# TSOC_GROVEY_ONE_R0_0.net
KiCad netlist of a schematic drawn in EAGLE
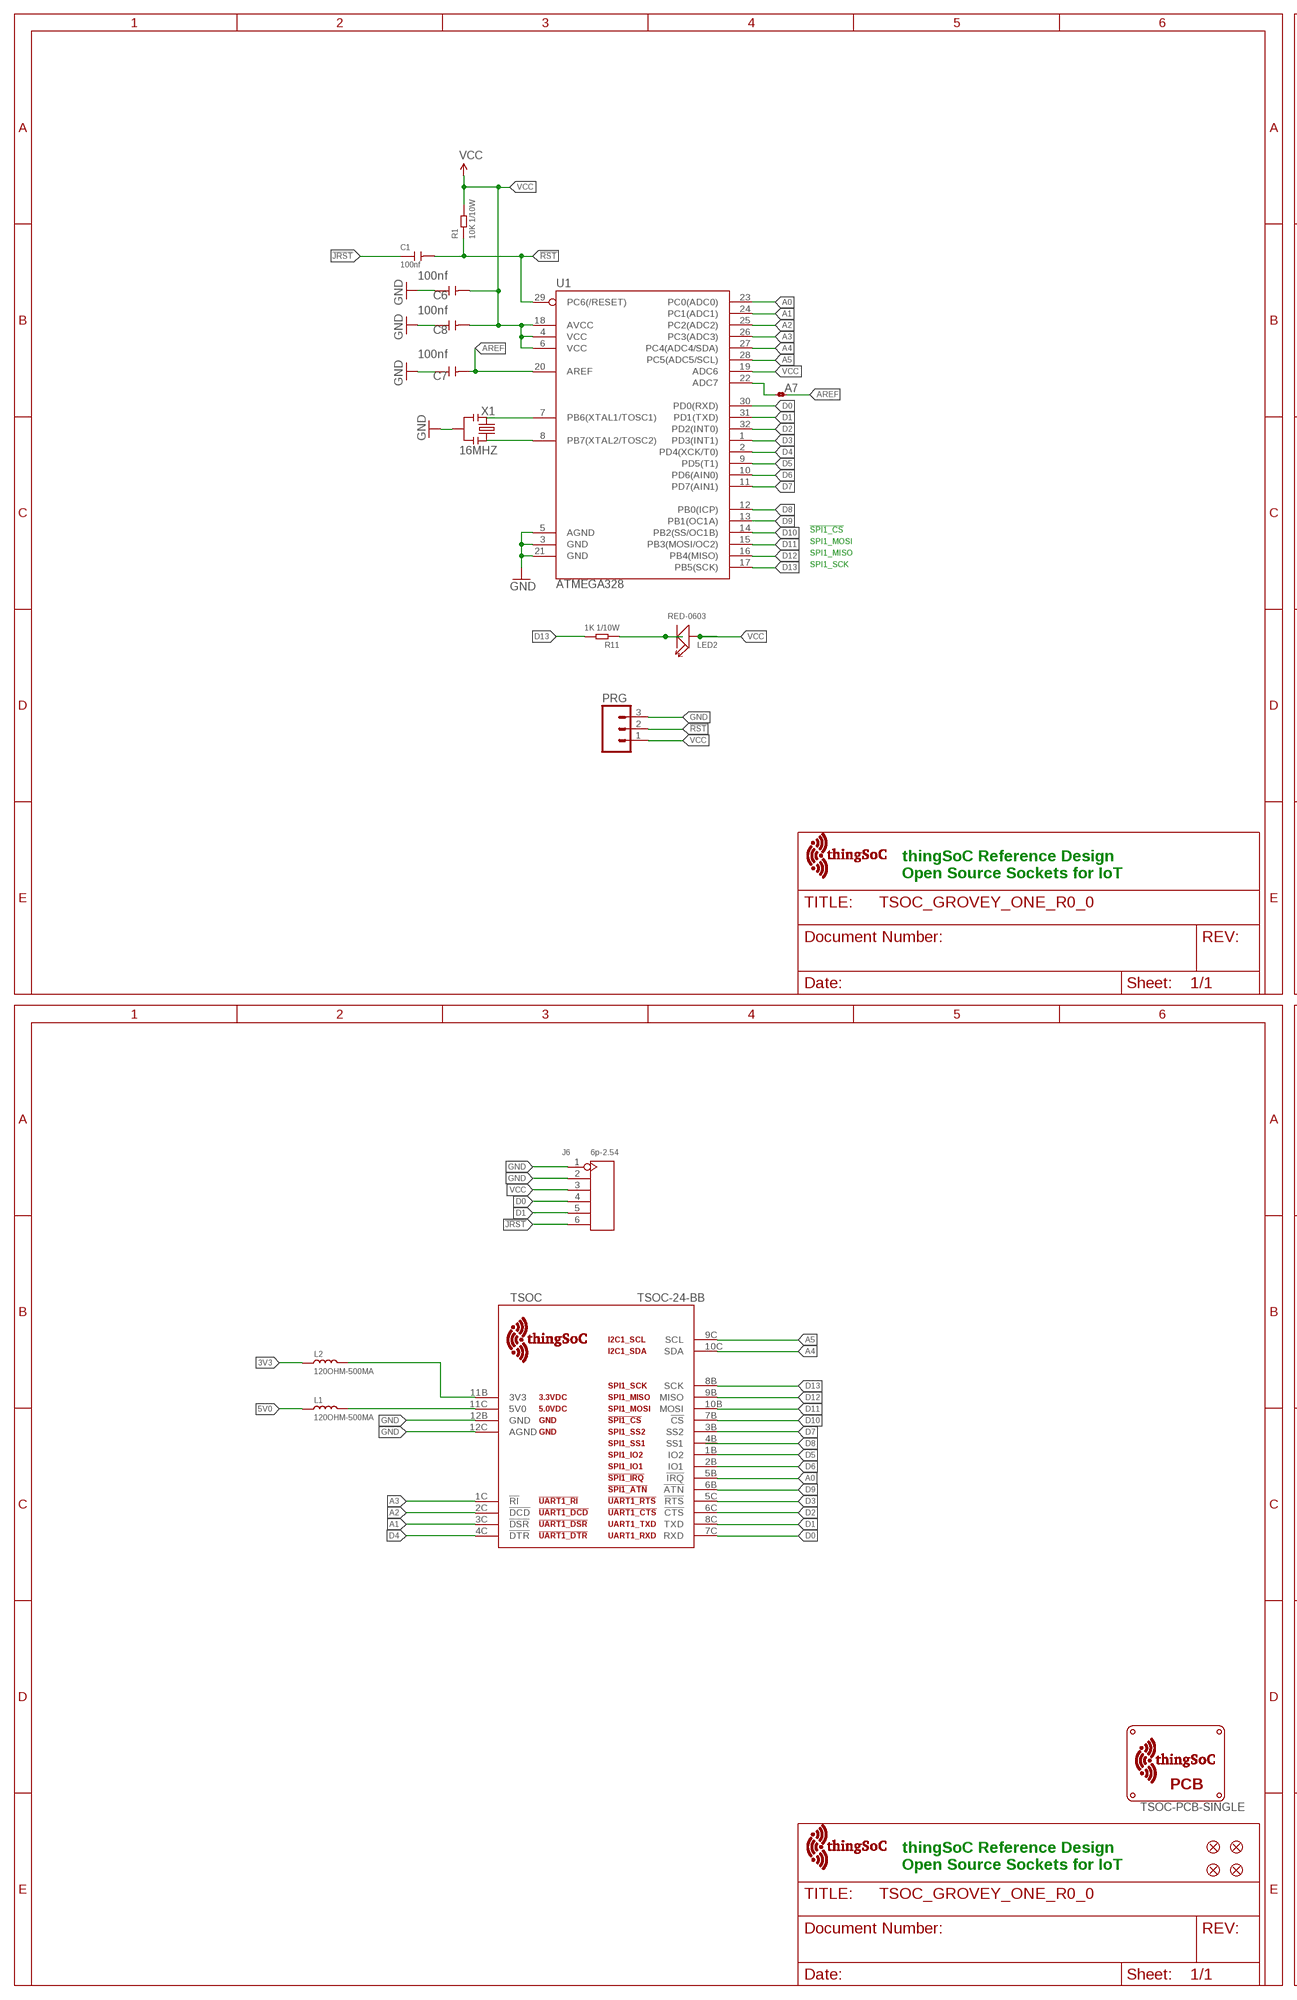
[diagram p0: schematic, sheet 1, part 1 of 2]
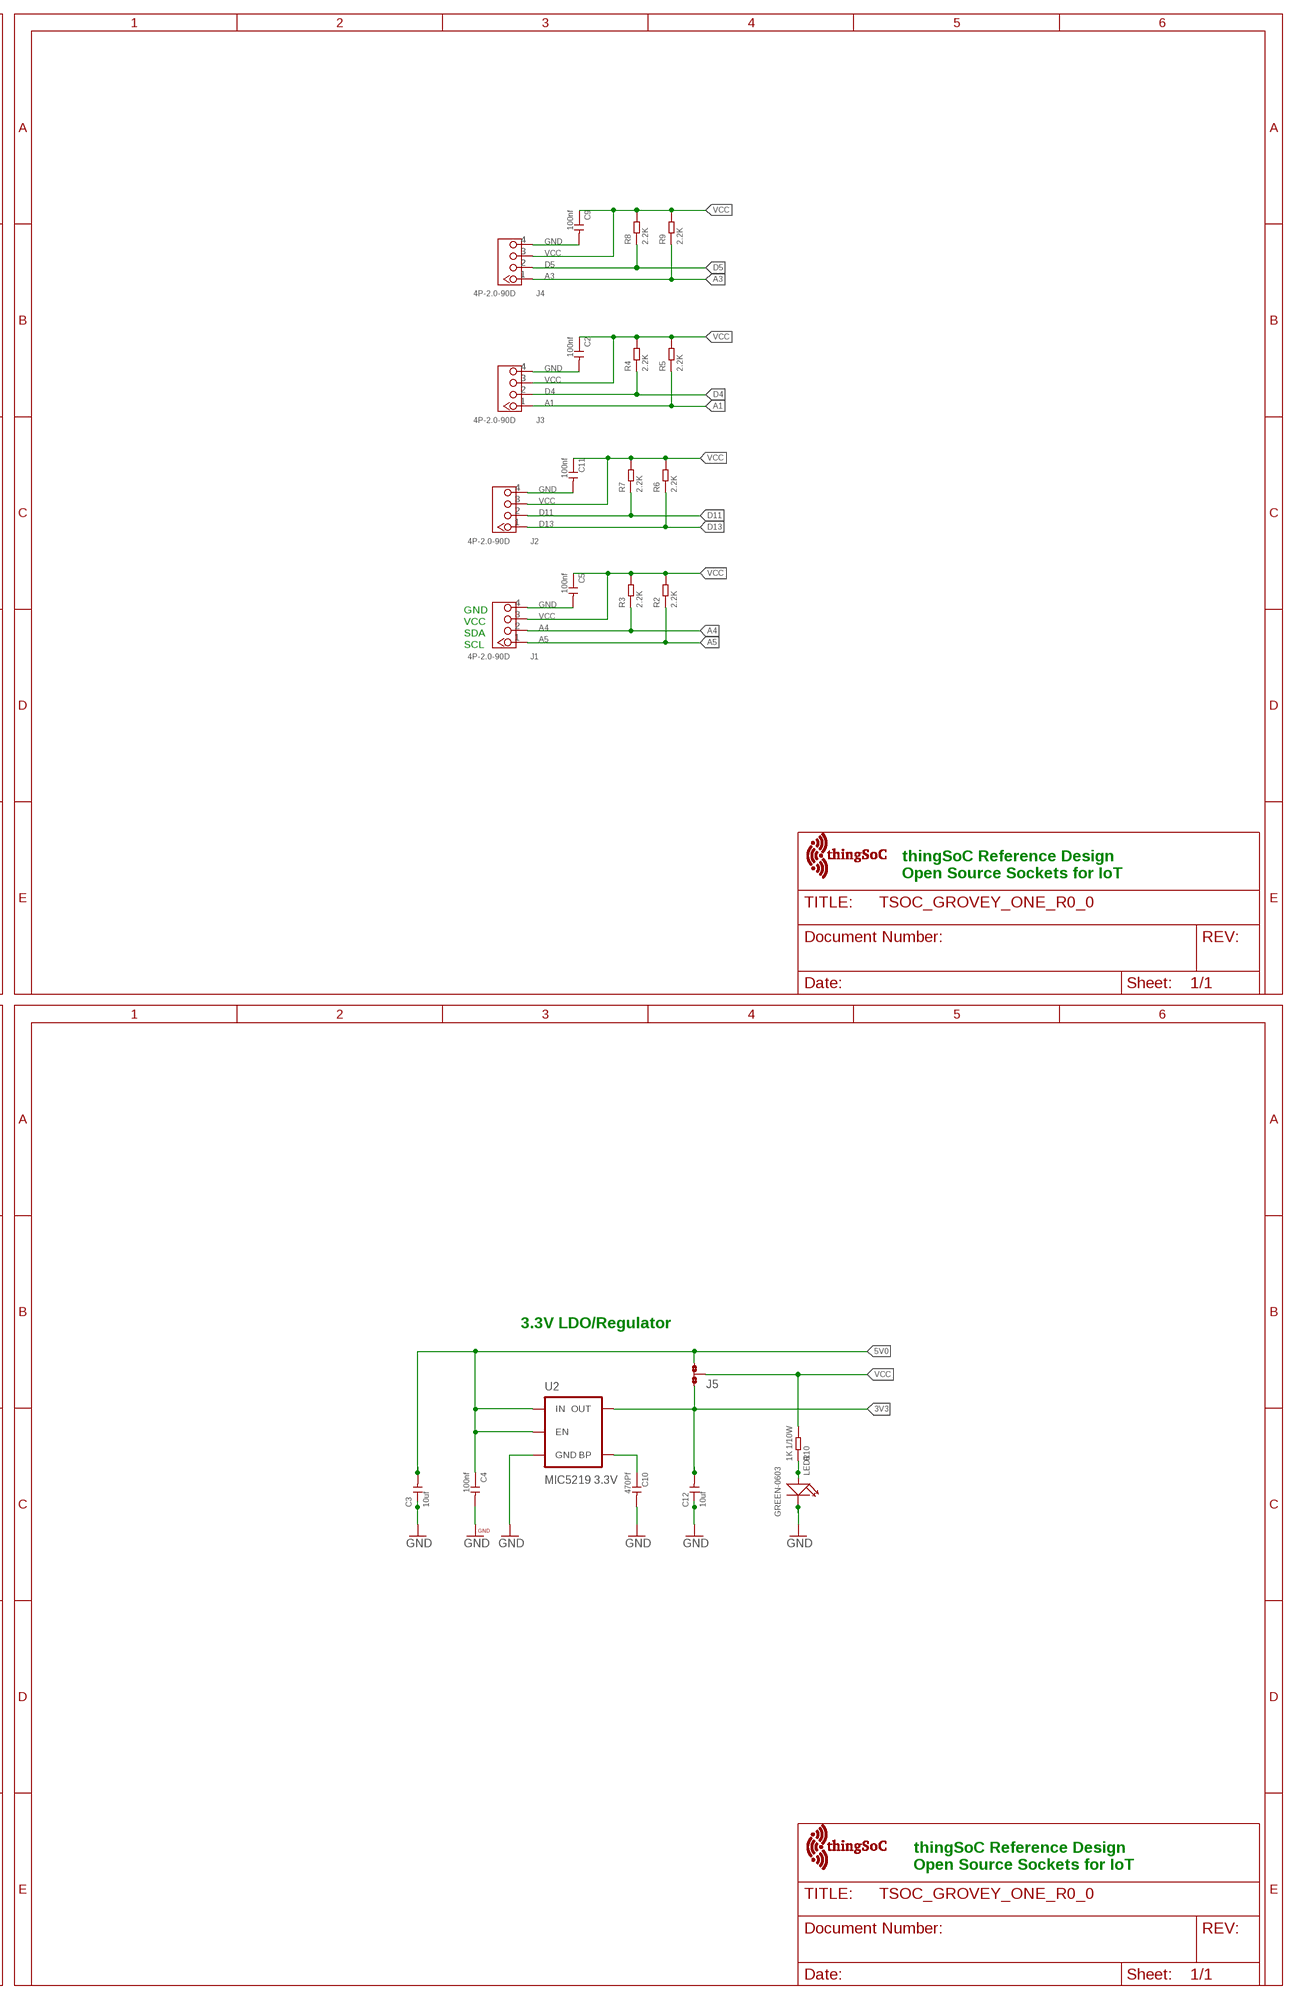
[diagram p1: schematic, sheet 1, part 2 of 2]

(export (version "E")
  (design (tool "Eeschema 10.0.6"))
  (components
    (comp (ref "$$U$2")
      (value "TSOC-PCB-SINGLE")
      (footprint "eagle-import:TSOC-BB-BRD-DIM")
      (libsource (lib "eagle-import") (part "TSOC-PCB-SINGLE"))
    )
    (comp (ref "A7")
      (value "JMP-2-NO")
      (footprint "eagle-import:JMP-2-NO")
      (libsource (lib "eagle-import") (part "JMP-2-NO"))
    )
    (comp (ref "C1")
      (value "100nf")
      (footprint "eagle-import:C0603")
      (fields (field (name "MPN") "CC0603KRX7R9BB104"))
      (libsource (lib "eagle-import") (part "CERAMIC-100NF-50V-10%-X7R(0603)"))
    )
    (comp (ref "C2")
      (value "100nf")
      (footprint "eagle-import:C0603")
      (fields (field (name "MPN") "CC0603KRX7R9BB104"))
      (libsource (lib "eagle-import") (part "CERAMIC-100NF-50V-10%-X7R(0603)"))
    )
    (comp (ref "C3")
      (value "10uf")
      (footprint "eagle-import:C0603")
      (fields (field (name "MPN") "CC0603KRX5R6BB106"))
      (libsource (lib "eagle-import") (part "CERAMIC-10UF-10V-10%-X5R(0603)"))
    )
    (comp (ref "C4")
      (value "100nf")
      (footprint "eagle-import:C0603")
      (fields (field (name "MPN") "CC0603KRX7R9BB104"))
      (libsource (lib "eagle-import") (part "CERAMIC-100NF-50V-10%-X7R(0603)"))
    )
    (comp (ref "C5")
      (value "100nf")
      (footprint "eagle-import:C0603")
      (fields (field (name "MPN") "CC0603KRX7R9BB104"))
      (libsource (lib "eagle-import") (part "CERAMIC-100NF-50V-10%-X7R(0603)"))
    )
    (comp (ref "C6")
      (value "100nf")
      (footprint "eagle-import:C0603")
      (fields (field (name "MPN") "CC0603KRX7R9BB104"))
      (libsource (lib "eagle-import") (part "CERAMIC-100NF-50V-10%-X7R(0603)"))
    )
    (comp (ref "C7")
      (value "100nf")
      (footprint "eagle-import:C0603")
      (fields (field (name "MPN") "CC0603KRX7R9BB104"))
      (libsource (lib "eagle-import") (part "CERAMIC-100NF-50V-10%-X7R(0603)"))
    )
    (comp (ref "C8")
      (value "100nf")
      (footprint "eagle-import:C0603")
      (fields (field (name "MPN") "CC0603KRX7R9BB104"))
      (libsource (lib "eagle-import") (part "CERAMIC-100NF-50V-10%-X7R(0603)"))
    )
    (comp (ref "C9")
      (value "100nf")
      (footprint "eagle-import:C0603")
      (fields (field (name "MPN") "CC0603KRX7R9BB104"))
      (libsource (lib "eagle-import") (part "CERAMIC-100NF-50V-10%-X7R(0603)"))
    )
    (comp (ref "C10")
      (value "470Pf")
      (footprint "eagle-import:C0603")
      (fields (field (name "MPN") "CC0603KRX7R9BB104"))
      (libsource (lib "eagle-import") (part "CERAMIC-100NF-50V-10%-X7R(0603)"))
    )
    (comp (ref "C11")
      (value "100nf")
      (footprint "eagle-import:C0603")
      (fields (field (name "MPN") "CC0603KRX7R9BB104"))
      (libsource (lib "eagle-import") (part "CERAMIC-100NF-50V-10%-X7R(0603)"))
    )
    (comp (ref "C12")
      (value "10uf")
      (footprint "eagle-import:C0603")
      (fields (field (name "MPN") "CC0603KRX5R6BB106"))
      (libsource (lib "eagle-import") (part "CERAMIC-10UF-10V-10%-X5R(0603)"))
    )
    (comp (ref "FID1")
      (value "FIDUCIALUFIDUCIAL")
      (footprint "eagle-import:MICRO-FIDUCIAL")
      (libsource (lib "eagle-import") (part "FIDUCIALUFIDUCIAL"))
    )
    (comp (ref "FID2")
      (value "FIDUCIALUFIDUCIAL")
      (footprint "eagle-import:MICRO-FIDUCIAL")
      (libsource (lib "eagle-import") (part "FIDUCIALUFIDUCIAL"))
    )
    (comp (ref "FID3")
      (value "FIDUCIALUFIDUCIAL")
      (footprint "eagle-import:MICRO-FIDUCIAL")
      (libsource (lib "eagle-import") (part "FIDUCIALUFIDUCIAL"))
    )
    (comp (ref "FID4")
      (value "FIDUCIALUFIDUCIAL")
      (footprint "eagle-import:MICRO-FIDUCIAL")
      (libsource (lib "eagle-import") (part "FIDUCIALUFIDUCIAL"))
    )
    (comp (ref "J1")
      (value "4P-2.0-90D")
      (footprint "eagle-import:HW4-2.0-90D")
      (libsource (lib "eagle-import") (part "GROVE-CONNECTOR-DIP-90D(4P-2.0)"))
    )
    (comp (ref "J2")
      (value "4P-2.0-90D")
      (footprint "eagle-import:HW4-2.0-90D")
      (libsource (lib "eagle-import") (part "GROVE-CONNECTOR-DIP-90D(4P-2.0)"))
    )
    (comp (ref "J3")
      (value "4P-2.0-90D")
      (footprint "eagle-import:HW4-2.0-90D")
      (libsource (lib "eagle-import") (part "GROVE-CONNECTOR-DIP-90D(4P-2.0)"))
    )
    (comp (ref "J4")
      (value "4P-2.0-90D")
      (footprint "eagle-import:HW4-2.0-90D")
      (libsource (lib "eagle-import") (part "GROVE-CONNECTOR-DIP-90D(4P-2.0)"))
    )
    (comp (ref "J5")
      (value "NO")
      (footprint "eagle-import:JMP-3-NO-PTH-2.54")
      (libsource (lib "eagle-import") (part "JMP-3-NO-PTH"))
    )
    (comp (ref "J6")
      (value "6p-2.54")
      (footprint "eagle-import:H6-2.54")
      (fields (field (name "MPN") "P125-1106A1BS116A1"))
      (libsource (lib "eagle-import") (part "DIP-BLACK-MALE-HEADER(6P-2.54)"))
    )
    (comp (ref "L1")
      (value "120OHM-500MA")
      (footprint "eagle-import:L0603")
      (fields (field (name "MPN") "BLM18AG121SN1D"))
      (libsource (lib "eagle-import") (part "SMD-FERRITE-CHIP-120-OHM-500MA(0603)"))
    )
    (comp (ref "L2")
      (value "120OHM-500MA")
      (footprint "eagle-import:L0603")
      (fields (field (name "MPN") "BLM18AG121SN1D"))
      (libsource (lib "eagle-import") (part "SMD-FERRITE-CHIP-120-OHM-500MA(0603)"))
    )
    (comp (ref "LED1")
      (value "GREEN-0603")
      (footprint "eagle-import:LED-0603")
      (fields (field (name "MPN") "19-217-G7C-AN1P2-3T"))
      (libsource (lib "eagle-import") (part "SMD-LED-CLEAR-GREEN(0603)"))
    )
    (comp (ref "LED2")
      (value "RED-0603")
      (footprint "eagle-import:LED-0603")
      (fields (field (name "MPN") "19-217-G7C-AN1P2-3T"))
      (libsource (lib "eagle-import") (part "SMD-LED-CLEAR-GREEN(0603)"))
    )
    (comp (ref "PRG")
      (value "M03PTH")
      (footprint "eagle-import:1X03")
      (libsource (lib "eagle-import") (part "M03PTH"))
    )
    (comp (ref "R1")
      (value "10K 1/10W")
      (footprint "eagle-import:R0603")
      (fields (field (name "MPN") "RC0603JR-0710KL"))
      (libsource (lib "eagle-import") (part "SMD-RES-10K-5%-1/10W(0603)"))
    )
    (comp (ref "R2")
      (value "2.2K")
      (footprint "eagle-import:R0603")
      (fields (field (name "MPN") "RC0603JR-072K2L"))
      (libsource (lib "eagle-import") (part "SMD-RES-2.2K-5%-1/10W(0603)"))
    )
    (comp (ref "R3")
      (value "2.2K")
      (footprint "eagle-import:R0603")
      (fields (field (name "MPN") "RC0603JR-072K2L"))
      (libsource (lib "eagle-import") (part "SMD-RES-2.2K-5%-1/10W(0603)"))
    )
    (comp (ref "R4")
      (value "2.2K")
      (footprint "eagle-import:R0603")
      (fields (field (name "MPN") "RC0603JR-072K2L"))
      (libsource (lib "eagle-import") (part "SMD-RES-2.2K-5%-1/10W(0603)"))
    )
    (comp (ref "R5")
      (value "2.2K")
      (footprint "eagle-import:R0603")
      (fields (field (name "MPN") "RC0603JR-072K2L"))
      (libsource (lib "eagle-import") (part "SMD-RES-2.2K-5%-1/10W(0603)"))
    )
    (comp (ref "R6")
      (value "2.2K")
      (footprint "eagle-import:R0603")
      (fields (field (name "MPN") "RC0603JR-072K2L"))
      (libsource (lib "eagle-import") (part "SMD-RES-2.2K-5%-1/10W(0603)"))
    )
    (comp (ref "R7")
      (value "2.2K")
      (footprint "eagle-import:R0603")
      (fields (field (name "MPN") "RC0603JR-072K2L"))
      (libsource (lib "eagle-import") (part "SMD-RES-2.2K-5%-1/10W(0603)"))
    )
    (comp (ref "R8")
      (value "2.2K")
      (footprint "eagle-import:R0603")
      (fields (field (name "MPN") "RC0603JR-072K2L"))
      (libsource (lib "eagle-import") (part "SMD-RES-2.2K-5%-1/10W(0603)"))
    )
    (comp (ref "R9")
      (value "2.2K")
      (footprint "eagle-import:R0603")
      (fields (field (name "MPN") "RC0603JR-072K2L"))
      (libsource (lib "eagle-import") (part "SMD-RES-2.2K-5%-1/10W(0603)"))
    )
    (comp (ref "R10")
      (value "1K 1/10W")
      (footprint "eagle-import:R0603")
      (fields (field (name "MPN") "RC0603JR-071KL"))
      (libsource (lib "eagle-import") (part "SMD-RES-1K-5%-1/10W(0603)"))
    )
    (comp (ref "R11")
      (value "1K 1/10W")
      (footprint "eagle-import:R0603")
      (fields (field (name "MPN") "RC0603JR-071KL"))
      (libsource (lib "eagle-import") (part "SMD-RES-1K-5%-1/10W(0603)"))
    )
    (comp (ref "TSOC")
      (value "TSOC-24-BB")
      (footprint "eagle-import:TSOC-BB-S24")
      (libsource (lib "eagle-import") (part "TSOC-24-BB"))
    )
    (comp (ref "U$1")
      (value "TSOC-LOGO-SMALL")
      (footprint "eagle-import:TSOC-LOGO-SML")
      (libsource (lib "eagle-import") (part "TSOC-LOGO-SMALL"))
    )
    (comp (ref "U$100")
      (value "TSOC-LOGO-SMALL")
      (footprint "eagle-import:TSOC-LOGO-SML")
      (libsource (lib "eagle-import") (part "TSOC-LOGO-SMALL"))
    )
    (comp (ref "U$101")
      (value "TSOC-LOGO-LRG")
      (footprint "eagle-import:TSOC-LOGO-LRG")
      (libsource (lib "eagle-import") (part "TSOC-LOGO-LRG"))
    )
    (comp (ref "U$103")
      (value "TSOC-LOGO-SMALL")
      (footprint "eagle-import:TSOC-LOGO-SML")
      (libsource (lib "eagle-import") (part "TSOC-LOGO-SMALL"))
    )
    (comp (ref "U1")
      (value "ATMEGA328")
      (footprint "eagle-import:TQFP32-08")
      (libsource (lib "eagle-import") (part "ATMEGA168"))
    )
    (comp (ref "U2")
      (value "MIC5219 3.3V")
      (footprint "eagle-import:SOT23-5")
      (libsource (lib "eagle-import") (part "V_REG_MIC52193.3V"))
    )
    (comp (ref "X1")
      (value "16MHZ")
      (footprint "eagle-import:X3-SMD-3.6X1.3X0.8MM")
      (fields (field (name "MPN") "CSTCE16M0V53-R0"))
      (libsource (lib "eagle-import") (part "SMD-RESONATOR-16MHZ-15PF-0.5%-40R(3P-3.2X1.3MM)"))
    )
  )
  (nets
    (net (code "1") (name "/~{JRST}") (class "Default")
      (node (ref "C1") (pin "1") (pinfunction "1_1") (pintype "passive"))
      (node (ref "J6") (pin "6") (pinfunction "6_6") (pintype "bidirectional"))
    )
    (net (code "2") (name "/~{RST}") (class "Default")
      (node (ref "C1") (pin "2") (pinfunction "2_2") (pintype "passive"))
      (node (ref "PRG") (pin "2") (pinfunction "2_2") (pintype "passive"))
      (node (ref "R1") (pin "1") (pinfunction "1_1") (pintype "passive"))
      (node (ref "U1") (pin "29") (pinfunction "PC6(/RESET)_29") (pintype "bidirectional"))
    )
    (net (code "3") (name "3V3") (class "Default")
      (node (ref "C12") (pin "2") (pinfunction "2_2") (pintype "passive"))
      (node (ref "J5") (pin "1") (pinfunction "1_1") (pintype "passive"))
      (node (ref "L2") (pin "1") (pinfunction "1_1") (pintype "passive"))
      (node (ref "U2") (pin "5") (pinfunction "OUT_5") (pintype "passive"))
    )
    (net (code "4") (name "5V0") (class "Default")
      (node (ref "C3") (pin "2") (pinfunction "2_2") (pintype "passive"))
      (node (ref "C4") (pin "1") (pinfunction "1_1") (pintype "passive"))
      (node (ref "J5") (pin "3") (pinfunction "3_3") (pintype "passive"))
      (node (ref "L1") (pin "1") (pinfunction "1_1") (pintype "passive"))
      (node (ref "U2") (pin "1") (pinfunction "IN_1") (pintype "input"))
      (node (ref "U2") (pin "3") (pinfunction "EN_3") (pintype "input"))
    )
    (net (code "5") (name "A0") (class "Default")
      (node (ref "TSOC") (pin "5B") (pinfunction "~{IRQ}_5B") (pintype "bidirectional"))
      (node (ref "U1") (pin "23") (pinfunction "PC0(ADC0)_23") (pintype "bidirectional"))
    )
    (net (code "6") (name "A1") (class "Default")
      (node (ref "J3") (pin "1") (pinfunction "1_1") (pintype "bidirectional"))
      (node (ref "R5") (pin "1") (pinfunction "1_1") (pintype "passive"))
      (node (ref "TSOC") (pin "3C") (pinfunction "~{DSR}_3C") (pintype "bidirectional"))
      (node (ref "U1") (pin "24") (pinfunction "PC1(ADC1)_24") (pintype "bidirectional"))
    )
    (net (code "7") (name "A2") (class "Default")
      (node (ref "TSOC") (pin "2C") (pinfunction "~{DCD}_2C") (pintype "bidirectional"))
      (node (ref "U1") (pin "25") (pinfunction "PC2(ADC2)_25") (pintype "bidirectional"))
    )
    (net (code "8") (name "A3") (class "Default")
      (node (ref "J4") (pin "1") (pinfunction "1_1") (pintype "bidirectional"))
      (node (ref "R9") (pin "1") (pinfunction "1_1") (pintype "passive"))
      (node (ref "TSOC") (pin "1C") (pinfunction "~{RI}_1C") (pintype "bidirectional"))
      (node (ref "U1") (pin "26") (pinfunction "PC3(ADC3)_26") (pintype "bidirectional"))
    )
    (net (code "9") (name "A4") (class "Default")
      (node (ref "J1") (pin "2") (pinfunction "2_2") (pintype "bidirectional"))
      (node (ref "R3") (pin "1") (pinfunction "1_1") (pintype "passive"))
      (node (ref "TSOC") (pin "10C") (pinfunction "SDA_10C") (pintype "bidirectional"))
      (node (ref "U1") (pin "27") (pinfunction "PC4(ADC4/SDA)_27") (pintype "bidirectional"))
    )
    (net (code "10") (name "A5") (class "Default")
      (node (ref "J1") (pin "1") (pinfunction "1_1") (pintype "bidirectional"))
      (node (ref "R2") (pin "1") (pinfunction "1_1") (pintype "passive"))
      (node (ref "TSOC") (pin "9C") (pinfunction "SCL_9C") (pintype "bidirectional"))
      (node (ref "U1") (pin "28") (pinfunction "PC5(ADC5/SCL)_28") (pintype "bidirectional"))
    )
    (net (code "11") (name "AREF") (class "Default")
      (node (ref "A7") (pin "2") (pinfunction "2_2") (pintype "passive"))
      (node (ref "C7") (pin "2") (pinfunction "2_2") (pintype "passive"))
      (node (ref "U1") (pin "20") (pinfunction "AREF_20") (pintype "bidirectional"))
    )
    (net (code "12") (name "D0") (class "Default")
      (node (ref "J6") (pin "4") (pinfunction "4_4") (pintype "bidirectional"))
      (node (ref "TSOC") (pin "7C") (pinfunction "RXD_7C") (pintype "bidirectional"))
      (node (ref "U1") (pin "30") (pinfunction "PD0(RXD)_30") (pintype "bidirectional"))
    )
    (net (code "13") (name "D1") (class "Default")
      (node (ref "J6") (pin "5") (pinfunction "5_5") (pintype "bidirectional"))
      (node (ref "TSOC") (pin "8C") (pinfunction "TXD_8C") (pintype "bidirectional"))
      (node (ref "U1") (pin "31") (pinfunction "PD1(TXD)_31") (pintype "bidirectional"))
    )
    (net (code "14") (name "D2") (class "Default")
      (node (ref "TSOC") (pin "6C") (pinfunction "~{CTS}_6C") (pintype "bidirectional"))
      (node (ref "U1") (pin "32") (pinfunction "PD2(INT0)_32") (pintype "bidirectional"))
    )
    (net (code "15") (name "D3") (class "Default")
      (node (ref "TSOC") (pin "5C") (pinfunction "~{RTS}_5C") (pintype "bidirectional"))
      (node (ref "U1") (pin "1") (pinfunction "PD3(INT1)_1") (pintype "bidirectional"))
    )
    (net (code "16") (name "D4") (class "Default")
      (node (ref "J3") (pin "2") (pinfunction "2_2") (pintype "bidirectional"))
      (node (ref "R4") (pin "1") (pinfunction "1_1") (pintype "passive"))
      (node (ref "TSOC") (pin "4C") (pinfunction "~{DTR}_4C") (pintype "bidirectional"))
      (node (ref "U1") (pin "2") (pinfunction "PD4(XCK/T0)_2") (pintype "bidirectional"))
    )
    (net (code "17") (name "D5") (class "Default")
      (node (ref "J4") (pin "2") (pinfunction "2_2") (pintype "bidirectional"))
      (node (ref "R8") (pin "1") (pinfunction "1_1") (pintype "passive"))
      (node (ref "TSOC") (pin "1B") (pinfunction "IO2_1B") (pintype "bidirectional"))
      (node (ref "U1") (pin "9") (pinfunction "PD5(T1)_9") (pintype "bidirectional"))
    )
    (net (code "18") (name "D6") (class "Default")
      (node (ref "TSOC") (pin "2B") (pinfunction "IO1_2B") (pintype "bidirectional"))
      (node (ref "U1") (pin "10") (pinfunction "PD6(AIN0)_10") (pintype "bidirectional"))
    )
    (net (code "19") (name "D7") (class "Default")
      (node (ref "TSOC") (pin "3B") (pinfunction "SS2_3B") (pintype "bidirectional"))
      (node (ref "U1") (pin "11") (pinfunction "PD7(AIN1)_11") (pintype "bidirectional"))
    )
    (net (code "20") (name "D8") (class "Default")
      (node (ref "TSOC") (pin "4B") (pinfunction "SS1_4B") (pintype "bidirectional"))
      (node (ref "U1") (pin "12") (pinfunction "PB0(ICP)_12") (pintype "bidirectional"))
    )
    (net (code "21") (name "D9") (class "Default")
      (node (ref "TSOC") (pin "6B") (pinfunction "~{ATN}_6B") (pintype "bidirectional"))
      (node (ref "U1") (pin "13") (pinfunction "PB1(OC1A)_13") (pintype "bidirectional"))
    )
    (net (code "22") (name "D10") (class "Default")
      (node (ref "TSOC") (pin "7B") (pinfunction "~{CS}_7B") (pintype "bidirectional"))
      (node (ref "U1") (pin "14") (pinfunction "PB2(SS/OC1B)_14") (pintype "bidirectional"))
    )
    (net (code "23") (name "D11") (class "Default")
      (node (ref "J2") (pin "2") (pinfunction "2_2") (pintype "bidirectional"))
      (node (ref "R7") (pin "1") (pinfunction "1_1") (pintype "passive"))
      (node (ref "TSOC") (pin "10B") (pinfunction "MOSI_10B") (pintype "bidirectional"))
      (node (ref "U1") (pin "15") (pinfunction "PB3(MOSI/OC2)_15") (pintype "bidirectional"))
    )
    (net (code "24") (name "D12") (class "Default")
      (node (ref "TSOC") (pin "9B") (pinfunction "MISO_9B") (pintype "bidirectional"))
      (node (ref "U1") (pin "16") (pinfunction "PB4(MISO)_16") (pintype "bidirectional"))
    )
    (net (code "25") (name "D13") (class "Default")
      (node (ref "J2") (pin "1") (pinfunction "1_1") (pintype "bidirectional"))
      (node (ref "R11") (pin "2") (pinfunction "2_2") (pintype "passive"))
      (node (ref "R6") (pin "1") (pinfunction "1_1") (pintype "passive"))
      (node (ref "TSOC") (pin "8B") (pinfunction "SCK_8B") (pintype "bidirectional"))
      (node (ref "U1") (pin "17") (pinfunction "PB5(SCK)_17") (pintype "bidirectional"))
    )
    (net (code "26") (name "GND") (class "Default")
      (node (ref "C10") (pin "2") (pinfunction "2_2") (pintype "passive"))
      (node (ref "C11") (pin "2") (pinfunction "2_2") (pintype "passive"))
      (node (ref "C12") (pin "1") (pinfunction "1_1") (pintype "passive"))
      (node (ref "C2") (pin "2") (pinfunction "2_2") (pintype "passive"))
      (node (ref "C3") (pin "1") (pinfunction "1_1") (pintype "passive"))
      (node (ref "C4") (pin "2") (pinfunction "2_2") (pintype "passive"))
      (node (ref "C5") (pin "2") (pinfunction "2_2") (pintype "passive"))
      (node (ref "C6") (pin "1") (pinfunction "1_1") (pintype "passive"))
      (node (ref "C7") (pin "1") (pinfunction "1_1") (pintype "passive"))
      (node (ref "C8") (pin "1") (pinfunction "1_1") (pintype "passive"))
      (node (ref "C9") (pin "2") (pinfunction "2_2") (pintype "passive"))
      (node (ref "J1") (pin "4") (pinfunction "4_4") (pintype "bidirectional"))
      (node (ref "J2") (pin "4") (pinfunction "4_4") (pintype "bidirectional"))
      (node (ref "J3") (pin "4") (pinfunction "4_4") (pintype "bidirectional"))
      (node (ref "J4") (pin "4") (pinfunction "4_4") (pintype "bidirectional"))
      (node (ref "J6") (pin "1") (pinfunction "1_1") (pintype "bidirectional"))
      (node (ref "J6") (pin "2") (pinfunction "2_2") (pintype "bidirectional"))
      (node (ref "LED1") (pin "-") (pinfunction "-_-") (pintype "passive"))
      (node (ref "PRG") (pin "3") (pinfunction "3_3") (pintype "passive"))
      (node (ref "TSOC") (pin "12B") (pinfunction "GND_12B") (pintype "bidirectional"))
      (node (ref "TSOC") (pin "12C") (pinfunction "AGND_12C") (pintype "bidirectional"))
      (node (ref "U1") (pin "21") (pinfunction "GND_21") (pintype "bidirectional"))
      (node (ref "U1") (pin "3") (pinfunction "GND_3") (pintype "bidirectional"))
      (node (ref "U1") (pin "5") (pinfunction "AGND_5") (pintype "bidirectional"))
      (node (ref "U2") (pin "2") (pinfunction "GND_2") (pintype "input"))
      (node (ref "X1") (pin "2") (pinfunction "2_2") (pintype "passive"))
    )
    (net (code "27") (name "Net-(LED1-Pad+)") (class "Default")
      (node (ref "LED1") (pin "+") (pinfunction "+_+") (pintype "passive"))
      (node (ref "R10") (pin "1") (pinfunction "1_1") (pintype "passive"))
    )
    (net (code "28") (name "Net-(LED2-Pad-)") (class "Default")
      (node (ref "LED2") (pin "-") (pinfunction "-_-") (pintype "passive"))
      (node (ref "R11") (pin "1") (pinfunction "1_1") (pintype "passive"))
    )
    (net (code "29") (name "Net-(TSOC-3V3)") (class "Default")
      (node (ref "L2") (pin "2") (pinfunction "2_2") (pintype "passive"))
      (node (ref "TSOC") (pin "11B") (pinfunction "3V3_11B") (pintype "bidirectional"))
    )
    (net (code "30") (name "Net-(TSOC-5V0)") (class "Default")
      (node (ref "L1") (pin "2") (pinfunction "2_2") (pintype "passive"))
      (node (ref "TSOC") (pin "11C") (pinfunction "5V0_11C") (pintype "bidirectional"))
    )
    (net (code "31") (name "Net-(U1-ADC7)") (class "Default")
      (node (ref "A7") (pin "1") (pinfunction "1_1") (pintype "passive"))
      (node (ref "U1") (pin "22") (pinfunction "ADC7_22") (pintype "bidirectional"))
    )
    (net (code "32") (name "Net-(U1-PB6(XTAL1{slash}TOSC1))") (class "Default")
      (node (ref "U1") (pin "7") (pinfunction "PB6(XTAL1/TOSC1)_7") (pintype "bidirectional"))
      (node (ref "X1") (pin "3") (pinfunction "3_3") (pintype "passive"))
    )
    (net (code "33") (name "Net-(U1-PB7(XTAL2{slash}TOSC2))") (class "Default")
      (node (ref "U1") (pin "8") (pinfunction "PB7(XTAL2/TOSC2)_8") (pintype "bidirectional"))
      (node (ref "X1") (pin "1") (pinfunction "1_1") (pintype "passive"))
    )
    (net (code "34") (name "Net-(U2-BP)") (class "Default")
      (node (ref "C10") (pin "1") (pinfunction "1_1") (pintype "passive"))
      (node (ref "U2") (pin "4") (pinfunction "BP_4") (pintype "input"))
    )
    (net (code "35") (name "VCC") (class "Default")
      (node (ref "C11") (pin "1") (pinfunction "1_1") (pintype "passive"))
      (node (ref "C2") (pin "1") (pinfunction "1_1") (pintype "passive"))
      (node (ref "C5") (pin "1") (pinfunction "1_1") (pintype "passive"))
      (node (ref "C6") (pin "2") (pinfunction "2_2") (pintype "passive"))
      (node (ref "C8") (pin "2") (pinfunction "2_2") (pintype "passive"))
      (node (ref "C9") (pin "1") (pinfunction "1_1") (pintype "passive"))
      (node (ref "J1") (pin "3") (pinfunction "3_3") (pintype "bidirectional"))
      (node (ref "J2") (pin "3") (pinfunction "3_3") (pintype "bidirectional"))
      (node (ref "J3") (pin "3") (pinfunction "3_3") (pintype "bidirectional"))
      (node (ref "J4") (pin "3") (pinfunction "3_3") (pintype "bidirectional"))
      (node (ref "J5") (pin "2") (pinfunction "2_2") (pintype "passive"))
      (node (ref "J6") (pin "3") (pinfunction "3_3") (pintype "bidirectional"))
      (node (ref "LED2") (pin "+") (pinfunction "+_+") (pintype "passive"))
      (node (ref "PRG") (pin "1") (pinfunction "1_1") (pintype "passive"))
      (node (ref "R1") (pin "2") (pinfunction "2_2") (pintype "passive"))
      (node (ref "R10") (pin "2") (pinfunction "2_2") (pintype "passive"))
      (node (ref "R2") (pin "2") (pinfunction "2_2") (pintype "passive"))
      (node (ref "R3") (pin "2") (pinfunction "2_2") (pintype "passive"))
      (node (ref "R4") (pin "2") (pinfunction "2_2") (pintype "passive"))
      (node (ref "R5") (pin "2") (pinfunction "2_2") (pintype "passive"))
      (node (ref "R6") (pin "2") (pinfunction "2_2") (pintype "passive"))
      (node (ref "R7") (pin "2") (pinfunction "2_2") (pintype "passive"))
      (node (ref "R8") (pin "2") (pinfunction "2_2") (pintype "passive"))
      (node (ref "R9") (pin "2") (pinfunction "2_2") (pintype "passive"))
      (node (ref "U1") (pin "18") (pinfunction "AVCC_18") (pintype "bidirectional"))
      (node (ref "U1") (pin "19") (pinfunction "ADC6_19") (pintype "bidirectional"))
      (node (ref "U1") (pin "4") (pinfunction "VCC_4") (pintype "bidirectional"))
      (node (ref "U1") (pin "6") (pinfunction "VCC_6") (pintype "bidirectional"))
    )
  )
)
